# Hierarchal.net
KiCad netlist of a schematic drawn in Altium Designer
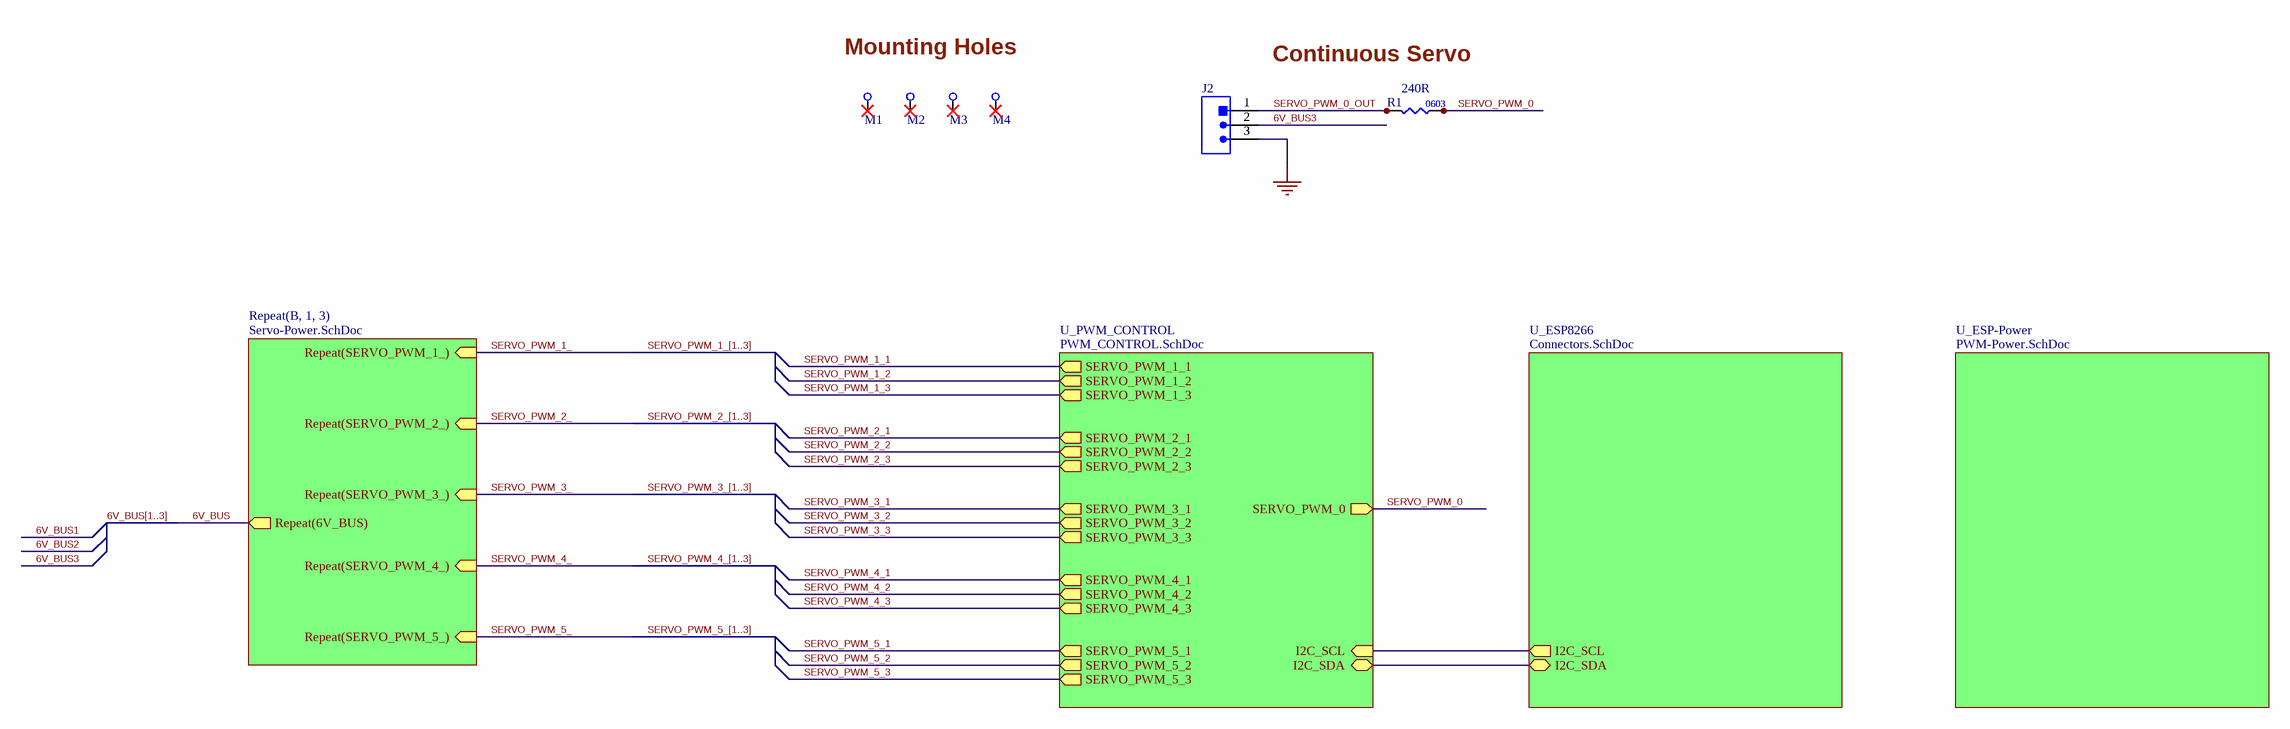
[diagram p0: Hierarchal.SchDoc]

(export (version "E")
  (design (tool "Eeschema 10.0.6"))
  (components
    (comp (ref "J2")
      (value "PRPC040SAAN-RC")
      (footprint "HEADER_3POS_2.54MM")
      (description "CONN HEADER VERT 3POS 2.54MM")
      (fields (field (name "MANUFACTURER") "Sullins"))
      (libsource (lib "PuttPilot") (part "PRPC040SAAN-RC"))
    )
    (comp (ref "M1")
      (value ".HOLE_M3")
      (footprint ".HOLE_M3")
      (description ".HOLE M3")
      (libsource (lib "PuttPilot") (part ".HOLE_M3"))
    )
    (comp (ref "M2")
      (value ".HOLE_M3")
      (footprint ".HOLE_M3")
      (description ".HOLE M3")
      (libsource (lib "PuttPilot") (part ".HOLE_M3"))
    )
    (comp (ref "M3")
      (value ".HOLE_M3")
      (footprint ".HOLE_M3")
      (description ".HOLE M3")
      (libsource (lib "PuttPilot") (part ".HOLE_M3"))
    )
    (comp (ref "M4")
      (value ".HOLE_M3")
      (footprint ".HOLE_M3")
      (description ".HOLE M3")
      (libsource (lib "PuttPilot") (part ".HOLE_M3"))
    )
    (comp (ref "R1")
      (value "RC0603FR-07240RL")
      (footprint ".RES_0603")
      (description "RES 240 OHM 0603")
      (fields
        (field (name "MANUFACTURER") "Yageo")
        (field (name "TOLERANCE") "1%")
        (field (name "RESISTANCE") "240R")
      )
      (libsource (lib "PuttPilot") (part "RC0603FR-07240RL"))
    )
  )
  (nets
    (net (code "4") (name "/6V_BUS3") (class "Default")
      (node (ref "J2") (pin "2") (pinfunction "2_2") (pintype "passive"))
    )
    (net (code "8") (name "/SERVO_PWM_0") (class "Default")
      (node (ref "R1") (pin "2") (pinfunction "2_2") (pintype "passive"))
    )
    (net (code "9") (name "/SERVO_PWM_0_OUT") (class "Default")
      (node (ref "J2") (pin "1") (pinfunction "1_1") (pintype "passive"))
      (node (ref "R1") (pin "1") (pinfunction "1_1") (pintype "passive"))
    )
    (net (code "35") (name "GND") (class "Default")
      (node (ref "J2") (pin "3") (pinfunction "3_3") (pintype "passive"))
    )
    (net (code "36") (name "unconnected-(M1-Pad1)") (class "Default")
      (node (ref "M1") (pin "1") (pinfunction "1_1") (pintype "passive+no_connect"))
    )
    (net (code "37") (name "unconnected-(M2-Pad1)") (class "Default")
      (node (ref "M2") (pin "1") (pinfunction "1_1") (pintype "passive+no_connect"))
    )
    (net (code "38") (name "unconnected-(M3-Pad1)") (class "Default")
      (node (ref "M3") (pin "1") (pinfunction "1_1") (pintype "passive+no_connect"))
    )
    (net (code "39") (name "unconnected-(M4-Pad1)") (class "Default")
      (node (ref "M4") (pin "1") (pinfunction "1_1") (pintype "passive+no_connect"))
    )
  )
)
